# LB_BIT_i19_ROLLERSWITCH-v02_rev1.net
KiCad netlist of a schematic drawn in EAGLE
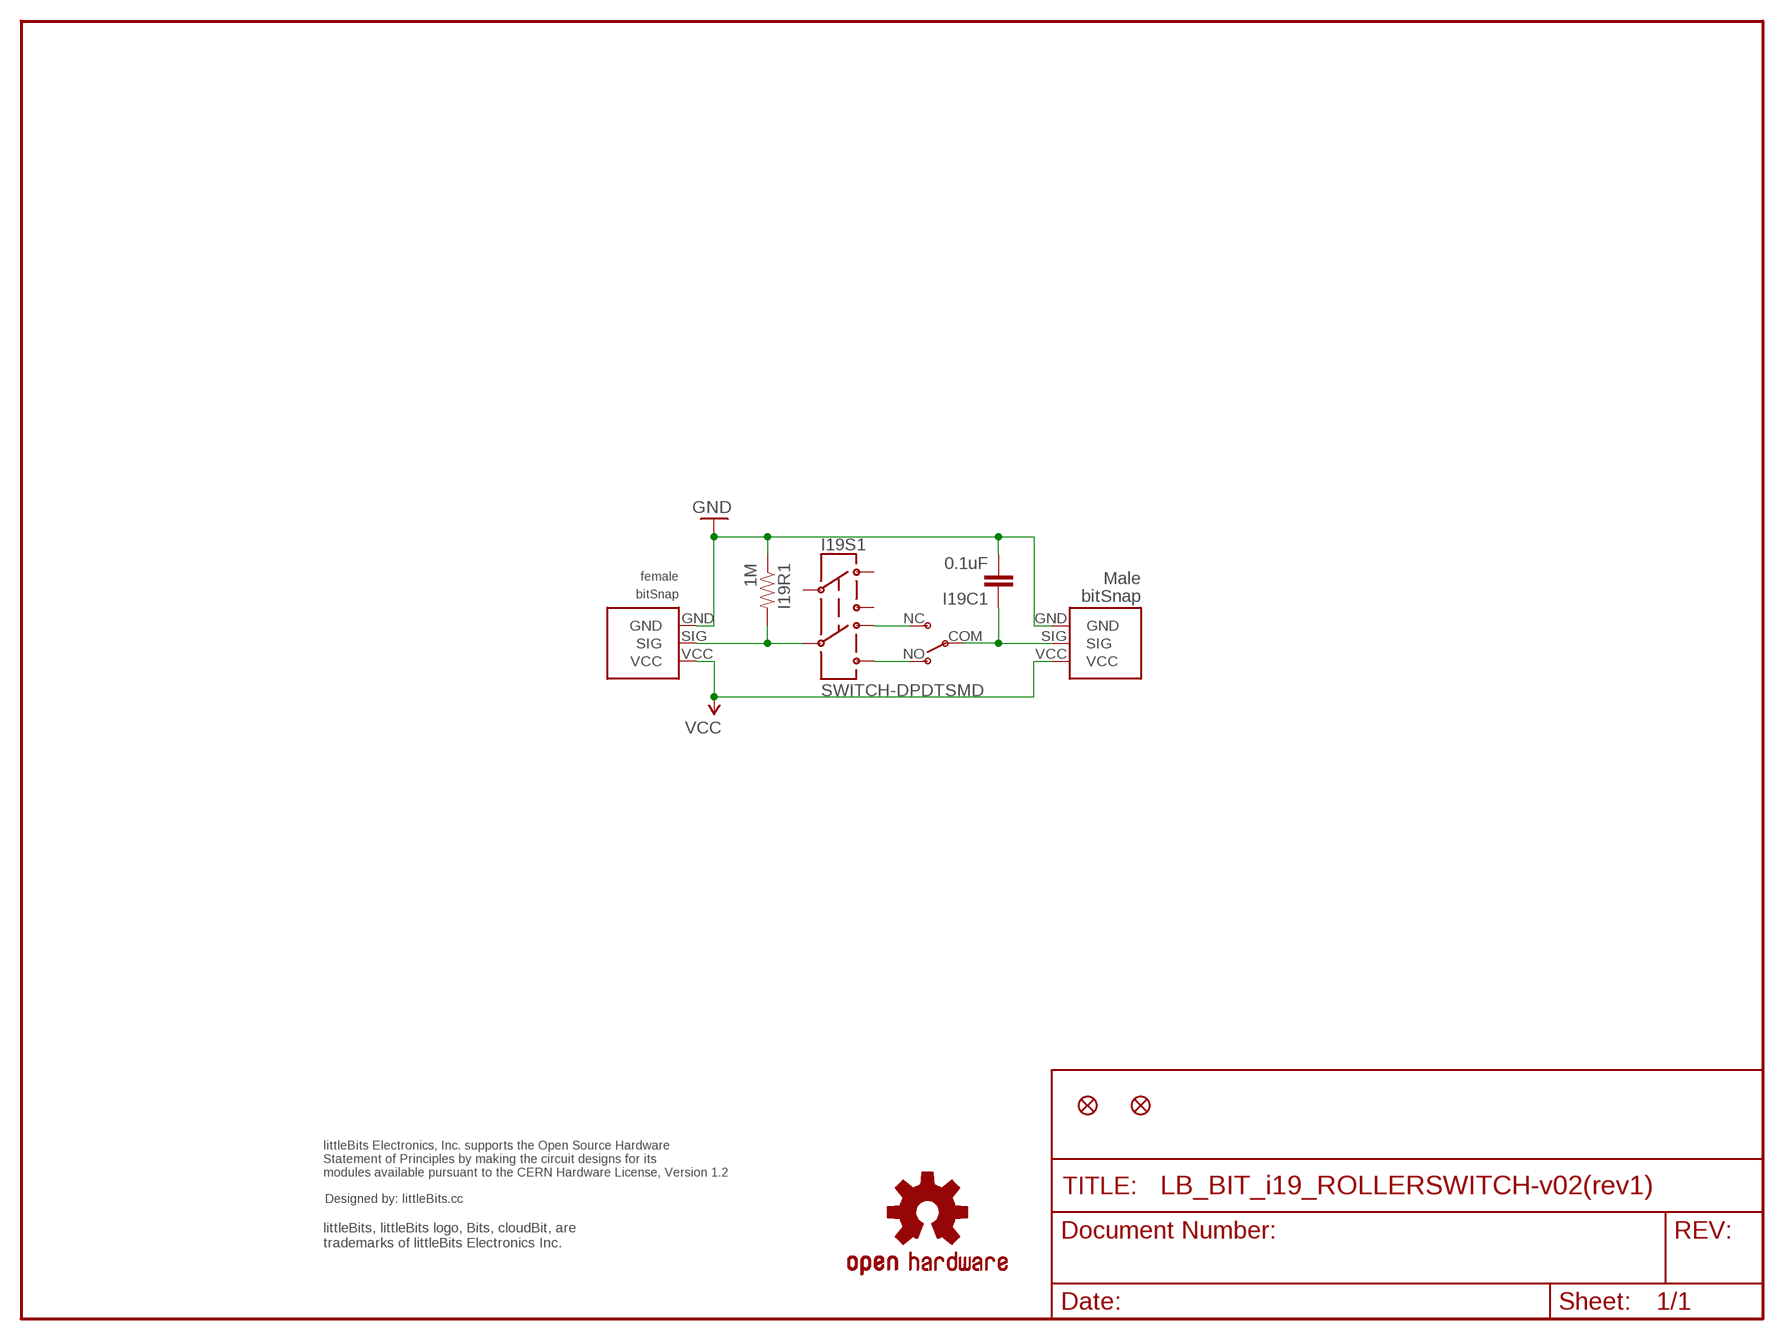
[diagram p0: schematic, sheet 1]

(export (version "E")
  (design (tool "Eeschema 10.0.6"))
  (components
    (comp (ref "I3BSF")
      (value "BITSNAP_FEMALE")
      (footprint "eagle-import:BITSNAP_FEMALE")
      (libsource (lib "eagle-import") (part "BITSNAP_FEMALE"))
    )
    (comp (ref "I3BSM")
      (value "BITSNAP_MALE")
      (footprint "eagle-import:BITSNAP_MALE")
      (libsource (lib "eagle-import") (part "BITSNAP_MALE"))
    )
    (comp (ref "I19C1")
      (value "0.1uF")
      (footprint "eagle-import:0603-CAP")
      (libsource (lib "eagle-import") (part "CAP0603-CAP"))
    )
    (comp (ref "I19FD1")
      (value "FIDUCIAL1X2")
      (footprint "eagle-import:FIDUCIAL-1X2")
      (libsource (lib "eagle-import") (part "FIDUCIAL1X2"))
    )
    (comp (ref "I19FD2")
      (value "FIDUCIAL1X2")
      (footprint "eagle-import:FIDUCIAL-1X2")
      (libsource (lib "eagle-import") (part "FIDUCIAL1X2"))
    )
    (comp (ref "I19R1")
      (value "1M")
      (footprint "eagle-import:0603-RES")
      (libsource (lib "eagle-import") (part "RESISTOR0603-RES"))
    )
    (comp (ref "I19S1")
      (value "SWITCH-DPDTSMD")
      (footprint "eagle-import:AYZ0202")
      (libsource (lib "eagle-import") (part "SWITCH-DPDTSMD"))
    )
    (comp (ref "I19SW2")
      (value "ROLLERSWITCH-OMRON-SS-5GL2DRIGHTANGLE")
      (footprint "eagle-import:ROLLERSWITCH-OMRON-D2F-01FL-A")
      (libsource (lib "eagle-import") (part "ROLLERSWITCH-OMRON-SS-5GL2DRIGHTANGLE"))
    )
    (comp (ref "U$1")
      (value "OSHWCREDIT")
      (footprint "eagle-import:OSHWCREDIT")
      (libsource (lib "eagle-import") (part "OSHWCREDIT"))
    )
    (comp (ref "U$3")
      (value "OSHW-LOGOL")
      (footprint "eagle-import:OSHW-LOGO-L")
      (libsource (lib "eagle-import") (part "OSHW-LOGOL"))
    )
  )
  (nets
    (net (code "1") (name "GND") (class "Default")
      (node (ref "I19C1") (pin "2") (pinfunction "2_2") (pintype "passive"))
      (node (ref "I19R1") (pin "1") (pinfunction "1_1") (pintype "passive"))
      (node (ref "I3BSF") (pin "GND") (pinfunction "GND_GND") (pintype "bidirectional"))
      (node (ref "I3BSM") (pin "GND") (pinfunction "GND_GND") (pintype "bidirectional"))
    )
    (net (code "2") (name "Net-(I19C1-Pad1)") (class "Default")
      (node (ref "I19C1") (pin "1") (pinfunction "1_1") (pintype "passive"))
      (node (ref "I19SW2") (pin "COM") (pinfunction "COM_COM") (pintype "passive"))
      (node (ref "I3BSM") (pin "SIG") (pinfunction "SIG_SIG") (pintype "bidirectional"))
    )
    (net (code "3") (name "Net-(I19R1-Pad2)") (class "Default")
      (node (ref "I19R1") (pin "2") (pinfunction "2_2") (pintype "passive"))
      (node (ref "I19S1") (pin "5") (pinfunction "5_5") (pintype "bidirectional"))
      (node (ref "I3BSF") (pin "SIG") (pinfunction "SIG_SIG") (pintype "bidirectional"))
    )
    (net (code "4") (name "Net-(I19S1-Pad4)") (class "Default")
      (node (ref "I19S1") (pin "4") (pinfunction "4_4") (pintype "bidirectional"))
      (node (ref "I19SW2") (pin "NC") (pinfunction "NC_NC") (pintype "passive"))
    )
    (net (code "5") (name "Net-(I19S1-Pad6)") (class "Default")
      (node (ref "I19S1") (pin "6") (pinfunction "6_6") (pintype "bidirectional"))
      (node (ref "I19SW2") (pin "NO") (pinfunction "NO_NO") (pintype "passive"))
    )
    (net (code "6") (name "VCC") (class "Default")
      (node (ref "I3BSF") (pin "VCC") (pinfunction "VCC_VCC") (pintype "bidirectional"))
      (node (ref "I3BSM") (pin "VCC") (pinfunction "VCC_VCC") (pintype "bidirectional"))
    )
    (net (code "7") (name "unconnected-(I19S1-Pad1)") (class "Default")
      (node (ref "I19S1") (pin "1") (pinfunction "1_1") (pintype "bidirectional"))
    )
    (net (code "8") (name "unconnected-(I19S1-Pad2)") (class "Default")
      (node (ref "I19S1") (pin "2") (pinfunction "2_2") (pintype "bidirectional"))
    )
    (net (code "9") (name "unconnected-(I19S1-Pad3)") (class "Default")
      (node (ref "I19S1") (pin "3") (pinfunction "3_3") (pintype "bidirectional"))
    )
  )
)
